# YonderDeep.net
KiCad netlist of a schematic drawn in EAGLE
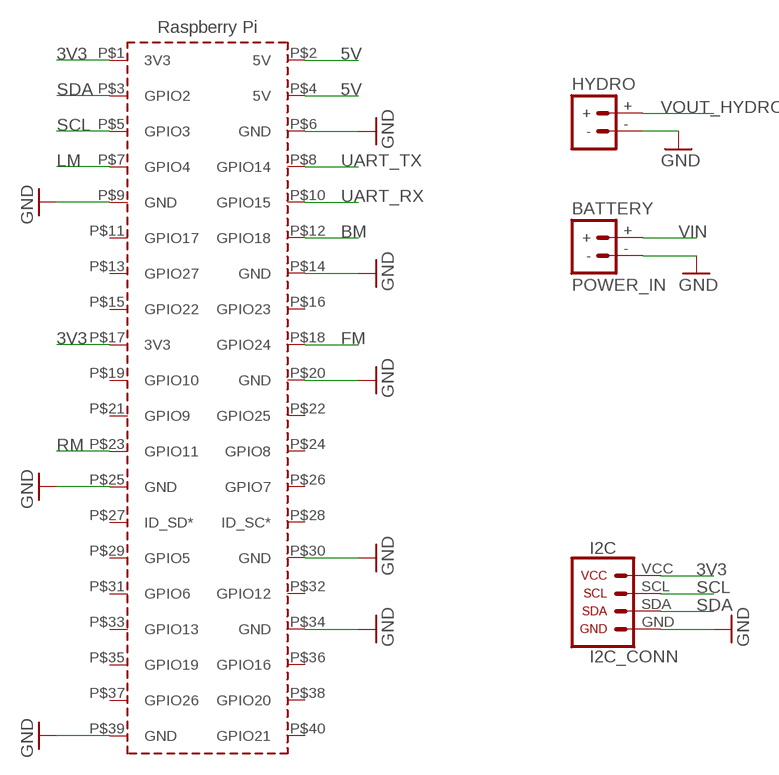
[diagram p0: schematic, sheet 1]
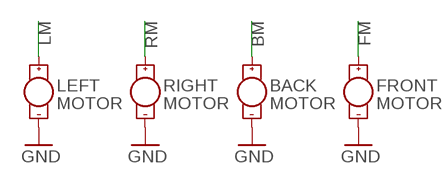
[diagram p1: schematic, sheet 2]
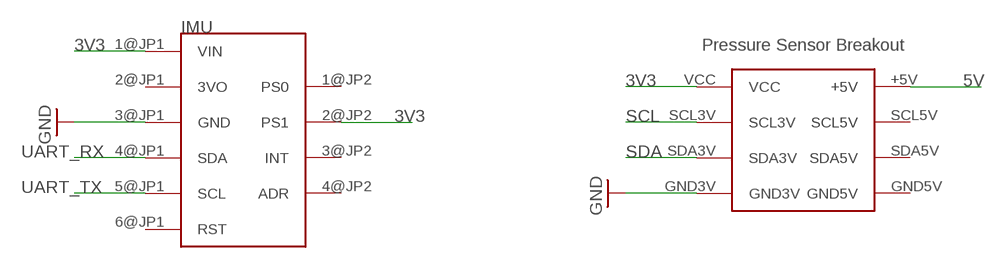
[diagram p2: schematic, sheet 3]
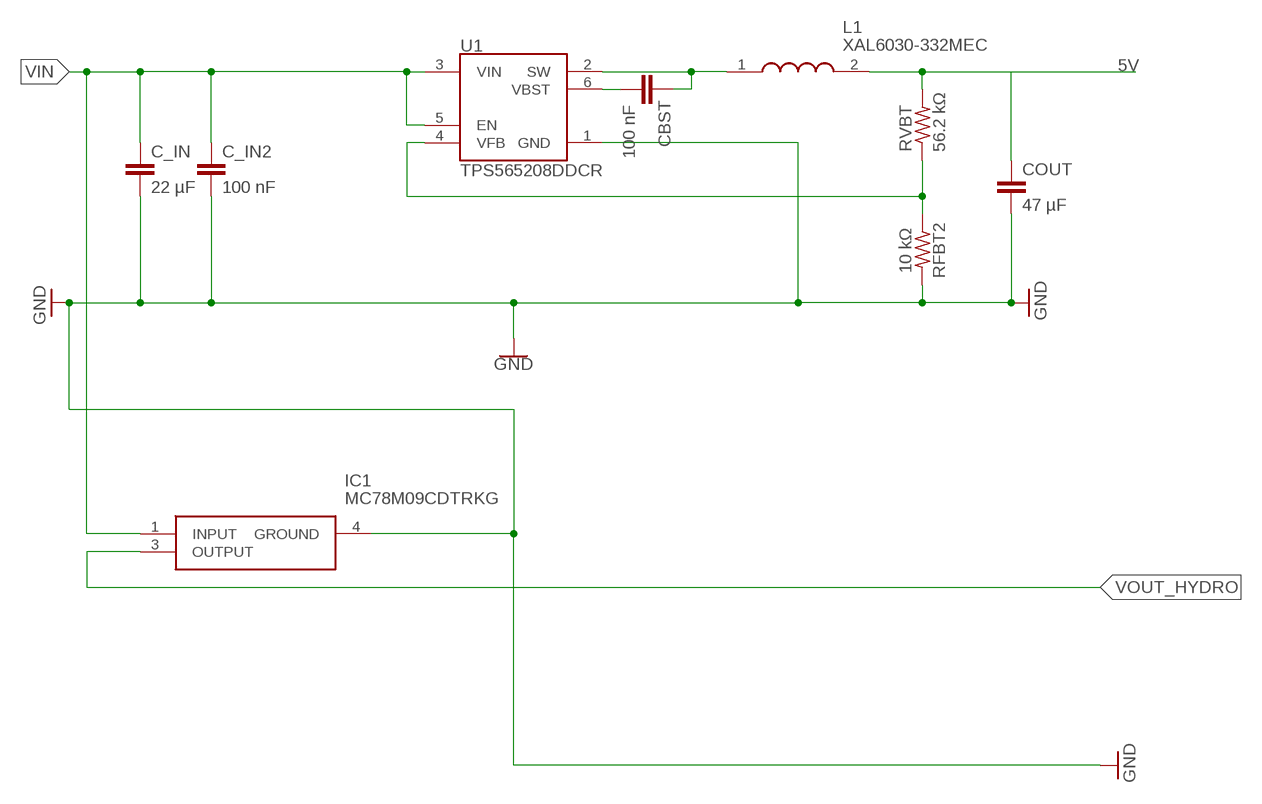
[diagram p3: schematic, sheet 4]

(export (version "E")
  (design (tool "Eeschema 10.0.6"))
  (components
    (comp (ref "BACK")
      (value "MOTOR")
      (footprint "eagle-import:1X02_PLUS_MINUS")
      (libsource (lib "eagle-import") (part "MOTOR"))
    )
    (comp (ref "FRONT")
      (value "MOTOR")
      (footprint "eagle-import:1X02_PLUS_MINUS")
      (libsource (lib "eagle-import") (part "MOTOR"))
    )
    (comp (ref "LEFT")
      (value "MOTOR")
      (footprint "eagle-import:1X02_PLUS_MINUS")
      (libsource (lib "eagle-import") (part "MOTOR"))
    )
    (comp (ref "RIGHT")
      (value "MOTOR")
      (footprint "eagle-import:1X02_PLUS_MINUS")
      (libsource (lib "eagle-import") (part "MOTOR"))
    )
    (comp (ref "IMU")
      (value "BNO055")
      (footprint "eagle-import:BNO055")
      (libsource (lib "eagle-import") (part "BNO055"))
    )
    (comp (ref "U$1")
      (value "PRESSURE_SENSOR_BREAKOUT")
      (footprint "eagle-import:BLUEROBOTICS_I2C_LVL_SHFT")
      (libsource (lib "eagle-import") (part "PRESSURE_SENSOR_BREAKOUT"))
    )
    (comp (ref "BATTERY")
      (value "POWER_IN")
      (footprint "eagle-import:TERMINAL")
      (libsource (lib "eagle-import") (part "POWER_IN"))
    )
    (comp (ref "HYDRO")
      (value "POWER_IN")
      (footprint "eagle-import:TERMINAL")
      (libsource (lib "eagle-import") (part "POWER_IN"))
    )
    (comp (ref "I2C")
      (value "I2C_CONN")
      (footprint "eagle-import:1X04")
      (libsource (lib "eagle-import") (part "I2C_CONN"))
    )
    (comp (ref "PCB1")
      (value "RPI3")
      (footprint "eagle-import:RPI3_CONN_ONLY")
      (libsource (lib "eagle-import") (part "RPI3"))
    )
    (comp (ref "CBST")
      (value "100 nF")
      (footprint "eagle-import:C0603K")
      (libsource (lib "eagle-import") (part "C0603C104Z3VACTU"))
    )
    (comp (ref "COUT")
      (value "47 µF")
      (footprint "eagle-import:C1210K")
      (libsource (lib "eagle-import") (part "TMK325ABJ476MM-P"))
    )
    (comp (ref "C_IN")
      (value "22 µF")
      (footprint "eagle-import:C1206K")
      (libsource (lib "eagle-import") (part "C3216JB1V226M160AC"))
    )
    (comp (ref "C_IN2")
      (value "100 nF")
      (footprint "eagle-import:C0603K")
      (libsource (lib "eagle-import") (part "C0603C104Z3VACTU"))
    )
    (comp (ref "IC1")
      (value "MC78M09CDTRKG")
      (footprint "eagle-import:TO229P991X238-4_3N")
      (fields (field (name "MOUSER_PART_NUMBER") "863-MC78M09CDTRKG"))
      (libsource (lib "eagle-import") (part "MC78M09CDTRKG"))
    )
    (comp (ref "L1")
      (value "XAL6030-332MEC")
      (footprint "eagle-import:XAL6030-122MEB")
      (fields (field (name "MOUSER_PART_NUMBER") "994-XAL6030-332MEC"))
      (libsource (lib "eagle-import") (part "XAL6030-332MEC"))
    )
    (comp (ref "RFBT2")
      (value "10 kΩ")
      (footprint "eagle-import:RESC1005X40")
      (fields (field (name "MF") "Stackpole Electronics") (field (name "MP") "RMCF0402FT10K0"))
      (libsource (lib "eagle-import") (part "RMCF0402FT10K0"))
    )
    (comp (ref "RVBT")
      (value "56.2 kΩ")
      (footprint "eagle-import:R0402")
      (libsource (lib "eagle-import") (part "AC0402FR-0756K2L"))
    )
    (comp (ref "U1")
      (value "TPS565208DDCR")
      (footprint "eagle-import:SOT95P280X110-6N")
      (fields (field (name "MF") "Texas Instruments"))
      (libsource (lib "eagle-import") (part "TPS565208DDCR"))
    )
  )
  (nets
    (net (code "1") (name "3V3") (class "Default")
      (node (ref "I2C") (pin "VCC") (pinfunction "VCC_VCC") (pintype "passive"))
      (node (ref "IMU") (pin "1@JP1") (pinfunction "VIN_1@JP1") (pintype "bidirectional"))
      (node (ref "IMU") (pin "2@JP2") (pinfunction "PS1_2@JP2") (pintype "bidirectional"))
      (node (ref "PCB1") (pin "P$1") (pinfunction "3V3_P$1") (pintype "bidirectional"))
      (node (ref "PCB1") (pin "P$17") (pinfunction "3V3_P$17") (pintype "bidirectional"))
      (node (ref "U$1") (pin "VCC") (pinfunction "VCC_VCC") (pintype "bidirectional"))
    )
    (net (code "2") (name "5V") (class "Default")
      (node (ref "COUT") (pin "1") (pinfunction "1_1") (pintype "passive"))
      (node (ref "L1") (pin "2") (pinfunction "2_2") (pintype "bidirectional"))
      (node (ref "PCB1") (pin "P$2") (pinfunction "5V_P$2") (pintype "bidirectional"))
      (node (ref "PCB1") (pin "P$4") (pinfunction "5V_P$4") (pintype "bidirectional"))
      (node (ref "RVBT") (pin "2") (pinfunction "2_2") (pintype "passive"))
      (node (ref "U$1") (pin "+5V") (pinfunction "+5V_+5V") (pintype "bidirectional"))
    )
    (net (code "3") (name "BM") (class "Default")
      (node (ref "BACK") (pin "+") (pinfunction "+_+") (pintype "bidirectional"))
      (node (ref "PCB1") (pin "P$12") (pinfunction "GPIO18_P$12") (pintype "bidirectional"))
    )
    (net (code "4") (name "FM") (class "Default")
      (node (ref "FRONT") (pin "+") (pinfunction "+_+") (pintype "bidirectional"))
      (node (ref "PCB1") (pin "P$18") (pinfunction "GPIO24_P$18") (pintype "bidirectional"))
    )
    (net (code "5") (name "GND") (class "Default")
      (node (ref "BACK") (pin "-") (pinfunction "-_-") (pintype "bidirectional"))
      (node (ref "BATTERY") (pin "-") (pinfunction "-_-") (pintype "passive"))
      (node (ref "COUT") (pin "2") (pinfunction "2_2") (pintype "passive"))
      (node (ref "C_IN") (pin "2") (pinfunction "2_2") (pintype "passive"))
      (node (ref "C_IN2") (pin "2") (pinfunction "2_2") (pintype "passive"))
      (node (ref "FRONT") (pin "-") (pinfunction "-_-") (pintype "bidirectional"))
      (node (ref "HYDRO") (pin "-") (pinfunction "-_-") (pintype "passive"))
      (node (ref "I2C") (pin "GND") (pinfunction "GND_GND") (pintype "passive"))
      (node (ref "IC1") (pin "4") (pinfunction "GROUND_4") (pintype "bidirectional"))
      (node (ref "IMU") (pin "3@JP1") (pinfunction "GND_3@JP1") (pintype "bidirectional"))
      (node (ref "LEFT") (pin "-") (pinfunction "-_-") (pintype "bidirectional"))
      (node (ref "PCB1") (pin "P$14") (pinfunction "GND_P$14") (pintype "bidirectional"))
      (node (ref "PCB1") (pin "P$20") (pinfunction "GND_P$20") (pintype "bidirectional"))
      (node (ref "PCB1") (pin "P$25") (pinfunction "GND_P$25") (pintype "bidirectional"))
      (node (ref "PCB1") (pin "P$30") (pinfunction "GND_P$30") (pintype "bidirectional"))
      (node (ref "PCB1") (pin "P$34") (pinfunction "GND_P$34") (pintype "bidirectional"))
      (node (ref "PCB1") (pin "P$39") (pinfunction "GND_P$39") (pintype "bidirectional"))
      (node (ref "PCB1") (pin "P$6") (pinfunction "GND_P$6") (pintype "bidirectional"))
      (node (ref "PCB1") (pin "P$9") (pinfunction "GND_P$9") (pintype "bidirectional"))
      (node (ref "RFBT2") (pin "2") (pinfunction "2_2") (pintype "passive"))
      (node (ref "RIGHT") (pin "-") (pinfunction "-_-") (pintype "bidirectional"))
      (node (ref "U$1") (pin "GND3V") (pinfunction "GND3V_GND3V") (pintype "bidirectional"))
      (node (ref "U1") (pin "1") (pinfunction "GND_1") (pintype "power_in"))
    )
    (net (code "6") (name "LM") (class "Default")
      (node (ref "LEFT") (pin "+") (pinfunction "+_+") (pintype "bidirectional"))
      (node (ref "PCB1") (pin "P$7") (pinfunction "GPIO4_P$7") (pintype "bidirectional"))
    )
    (net (code "7") (name "Net-(U1-SW)") (class "Default")
      (node (ref "CBST") (pin "1") (pinfunction "1_1") (pintype "passive"))
      (node (ref "L1") (pin "1") (pinfunction "1_1") (pintype "bidirectional"))
      (node (ref "U1") (pin "2") (pinfunction "SW_2") (pintype "output"))
    )
    (net (code "8") (name "Net-(U1-VBST)") (class "Default")
      (node (ref "CBST") (pin "2") (pinfunction "2_2") (pintype "passive"))
      (node (ref "U1") (pin "6") (pinfunction "VBST_6") (pintype "output"))
    )
    (net (code "9") (name "Net-(U1-VFB)") (class "Default")
      (node (ref "RFBT2") (pin "1") (pinfunction "1_1") (pintype "passive"))
      (node (ref "RVBT") (pin "1") (pinfunction "1_1") (pintype "passive"))
      (node (ref "U1") (pin "4") (pinfunction "VFB_4") (pintype "input"))
    )
    (net (code "10") (name "RM") (class "Default")
      (node (ref "PCB1") (pin "P$23") (pinfunction "GPIO11_P$23") (pintype "bidirectional"))
      (node (ref "RIGHT") (pin "+") (pinfunction "+_+") (pintype "bidirectional"))
    )
    (net (code "11") (name "SCL") (class "Default")
      (node (ref "I2C") (pin "SCL") (pinfunction "SCL_SCL") (pintype "passive"))
      (node (ref "PCB1") (pin "P$5") (pinfunction "GPIO3_P$5") (pintype "bidirectional"))
      (node (ref "U$1") (pin "SCL3V") (pinfunction "SCL3V_SCL3V") (pintype "bidirectional"))
    )
    (net (code "12") (name "SDA") (class "Default")
      (node (ref "I2C") (pin "SDA") (pinfunction "SDA_SDA") (pintype "passive"))
      (node (ref "PCB1") (pin "P$3") (pinfunction "GPIO2_P$3") (pintype "bidirectional"))
      (node (ref "U$1") (pin "SDA3V") (pinfunction "SDA3V_SDA3V") (pintype "bidirectional"))
    )
    (net (code "13") (name "UART_RX") (class "Default")
      (node (ref "IMU") (pin "4@JP1") (pinfunction "SDA_4@JP1") (pintype "bidirectional"))
      (node (ref "PCB1") (pin "P$10") (pinfunction "GPIO15_P$10") (pintype "bidirectional"))
    )
    (net (code "14") (name "UART_TX") (class "Default")
      (node (ref "IMU") (pin "5@JP1") (pinfunction "SCL_5@JP1") (pintype "bidirectional"))
      (node (ref "PCB1") (pin "P$8") (pinfunction "GPIO14_P$8") (pintype "bidirectional"))
    )
    (net (code "15") (name "VIN") (class "Default")
      (node (ref "BATTERY") (pin "+") (pinfunction "+_+") (pintype "passive"))
      (node (ref "C_IN") (pin "1") (pinfunction "1_1") (pintype "passive"))
      (node (ref "C_IN2") (pin "1") (pinfunction "1_1") (pintype "passive"))
      (node (ref "IC1") (pin "1") (pinfunction "INPUT_1") (pintype "bidirectional"))
      (node (ref "U1") (pin "3") (pinfunction "VIN_3") (pintype "input"))
      (node (ref "U1") (pin "5") (pinfunction "EN_5") (pintype "input"))
    )
    (net (code "16") (name "VOUT_HYDRO") (class "Default")
      (node (ref "HYDRO") (pin "+") (pinfunction "+_+") (pintype "passive"))
      (node (ref "IC1") (pin "3") (pinfunction "OUTPUT_3") (pintype "bidirectional"))
    )
    (net (code "17") (name "unconnected-(IMU-3VO-Pad2@JP1)") (class "Default")
      (node (ref "IMU") (pin "2@JP1") (pinfunction "3VO_2@JP1") (pintype "bidirectional"))
    )
    (net (code "18") (name "unconnected-(IMU-ADR-Pad4@JP2)") (class "Default")
      (node (ref "IMU") (pin "4@JP2") (pinfunction "ADR_4@JP2") (pintype "bidirectional"))
    )
    (net (code "19") (name "unconnected-(IMU-INT-Pad3@JP2)") (class "Default")
      (node (ref "IMU") (pin "3@JP2") (pinfunction "INT_3@JP2") (pintype "bidirectional"))
    )
    (net (code "20") (name "unconnected-(IMU-PS0-Pad1@JP2)") (class "Default")
      (node (ref "IMU") (pin "1@JP2") (pinfunction "PS0_1@JP2") (pintype "bidirectional"))
    )
    (net (code "21") (name "unconnected-(IMU-RST-Pad6@JP1)") (class "Default")
      (node (ref "IMU") (pin "6@JP1") (pinfunction "RST_6@JP1") (pintype "bidirectional"))
    )
    (net (code "22") (name "unconnected-(PCB1-GPIO5-PadP$29)") (class "Default")
      (node (ref "PCB1") (pin "P$29") (pinfunction "GPIO5_P$29") (pintype "bidirectional"))
    )
    (net (code "23") (name "unconnected-(PCB1-GPIO6-PadP$31)") (class "Default")
      (node (ref "PCB1") (pin "P$31") (pinfunction "GPIO6_P$31") (pintype "bidirectional"))
    )
    (net (code "24") (name "unconnected-(PCB1-GPIO7-PadP$26)") (class "Default")
      (node (ref "PCB1") (pin "P$26") (pinfunction "GPIO7_P$26") (pintype "bidirectional"))
    )
    (net (code "25") (name "unconnected-(PCB1-GPIO8-PadP$24)") (class "Default")
      (node (ref "PCB1") (pin "P$24") (pinfunction "GPIO8_P$24") (pintype "bidirectional"))
    )
    (net (code "26") (name "unconnected-(PCB1-GPIO9-PadP$21)") (class "Default")
      (node (ref "PCB1") (pin "P$21") (pinfunction "GPIO9_P$21") (pintype "bidirectional"))
    )
    (net (code "27") (name "unconnected-(PCB1-GPIO10-PadP$19)") (class "Default")
      (node (ref "PCB1") (pin "P$19") (pinfunction "GPIO10_P$19") (pintype "bidirectional"))
    )
    (net (code "28") (name "unconnected-(PCB1-GPIO12-PadP$32)") (class "Default")
      (node (ref "PCB1") (pin "P$32") (pinfunction "GPIO12_P$32") (pintype "bidirectional"))
    )
    (net (code "29") (name "unconnected-(PCB1-GPIO13-PadP$33)") (class "Default")
      (node (ref "PCB1") (pin "P$33") (pinfunction "GPIO13_P$33") (pintype "bidirectional"))
    )
    (net (code "30") (name "unconnected-(PCB1-GPIO16-PadP$36)") (class "Default")
      (node (ref "PCB1") (pin "P$36") (pinfunction "GPIO16_P$36") (pintype "bidirectional"))
    )
    (net (code "31") (name "unconnected-(PCB1-GPIO17-PadP$11)") (class "Default")
      (node (ref "PCB1") (pin "P$11") (pinfunction "GPIO17_P$11") (pintype "bidirectional"))
    )
    (net (code "32") (name "unconnected-(PCB1-GPIO19-PadP$35)") (class "Default")
      (node (ref "PCB1") (pin "P$35") (pinfunction "GPIO19_P$35") (pintype "bidirectional"))
    )
    (net (code "33") (name "unconnected-(PCB1-GPIO20-PadP$38)") (class "Default")
      (node (ref "PCB1") (pin "P$38") (pinfunction "GPIO20_P$38") (pintype "bidirectional"))
    )
    (net (code "34") (name "unconnected-(PCB1-GPIO21-PadP$40)") (class "Default")
      (node (ref "PCB1") (pin "P$40") (pinfunction "GPIO21_P$40") (pintype "bidirectional"))
    )
    (net (code "35") (name "unconnected-(PCB1-GPIO22-PadP$15)") (class "Default")
      (node (ref "PCB1") (pin "P$15") (pinfunction "GPIO22_P$15") (pintype "bidirectional"))
    )
    (net (code "36") (name "unconnected-(PCB1-GPIO23-PadP$16)") (class "Default")
      (node (ref "PCB1") (pin "P$16") (pinfunction "GPIO23_P$16") (pintype "bidirectional"))
    )
    (net (code "37") (name "unconnected-(PCB1-GPIO25-PadP$22)") (class "Default")
      (node (ref "PCB1") (pin "P$22") (pinfunction "GPIO25_P$22") (pintype "bidirectional"))
    )
    (net (code "38") (name "unconnected-(PCB1-GPIO26-PadP$37)") (class "Default")
      (node (ref "PCB1") (pin "P$37") (pinfunction "GPIO26_P$37") (pintype "bidirectional"))
    )
    (net (code "39") (name "unconnected-(PCB1-GPIO27-PadP$13)") (class "Default")
      (node (ref "PCB1") (pin "P$13") (pinfunction "GPIO27_P$13") (pintype "bidirectional"))
    )
    (net (code "40") (name "unconnected-(PCB1-ID_SC*-PadP$28)") (class "Default")
      (node (ref "PCB1") (pin "P$28") (pinfunction "ID_SC*_P$28") (pintype "bidirectional"))
    )
    (net (code "41") (name "unconnected-(PCB1-ID_SD*-PadP$27)") (class "Default")
      (node (ref "PCB1") (pin "P$27") (pinfunction "ID_SD*_P$27") (pintype "bidirectional"))
    )
    (net (code "42") (name "unconnected-(U$1-PadGND5V)") (class "Default")
      (node (ref "U$1") (pin "GND5V") (pinfunction "GND5V_GND5V") (pintype "bidirectional"))
    )
    (net (code "43") (name "unconnected-(U$1-PadSCL5V)") (class "Default")
      (node (ref "U$1") (pin "SCL5V") (pinfunction "SCL5V_SCL5V") (pintype "bidirectional"))
    )
    (net (code "44") (name "unconnected-(U$1-PadSDA5V)") (class "Default")
      (node (ref "U$1") (pin "SDA5V") (pinfunction "SDA5V_SDA5V") (pintype "bidirectional"))
    )
  )
)
